# SCFG.net
KiCad netlist of a schematic drawn in EAGLE
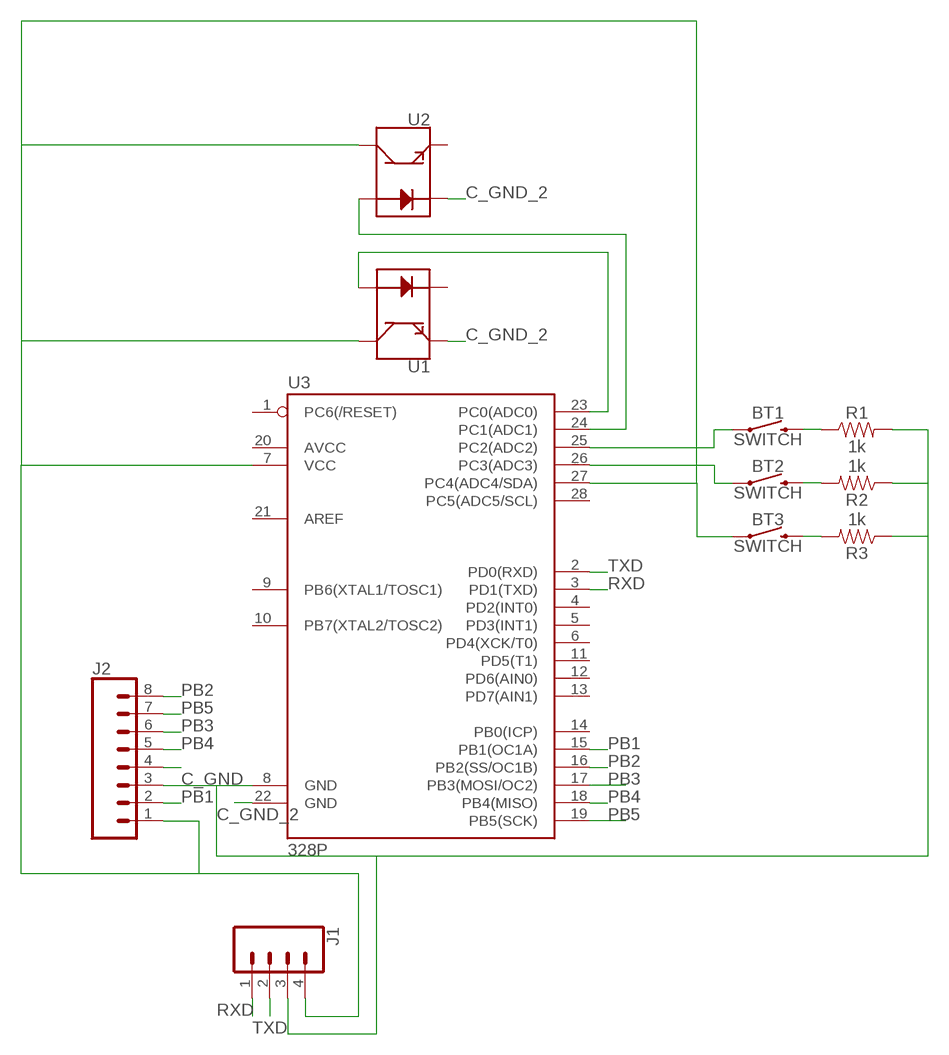
[diagram p0: schematic, sheet 1]

(export (version "E")
  (design (tool "Eeschema 10.0.6"))
  (components
    (comp (ref "BT1")
      (value "SWITCH")
      (footprint "eagle-import:TACTILE_SWITCH_PTH_6.0MM_KIT")
      (libsource (lib "eagle-import") (part "MOMENTARY-SWITCH-SPST-PTH-6.0MM-KIT"))
    )
    (comp (ref "BT2")
      (value "SWITCH")
      (footprint "eagle-import:TACTILE_SWITCH_PTH_6.0MM_KIT")
      (libsource (lib "eagle-import") (part "MOMENTARY-SWITCH-SPST-PTH-6.0MM-KIT"))
    )
    (comp (ref "BT3")
      (value "SWITCH")
      (footprint "eagle-import:TACTILE_SWITCH_PTH_6.0MM_KIT")
      (libsource (lib "eagle-import") (part "MOMENTARY-SWITCH-SPST-PTH-6.0MM-KIT"))
    )
    (comp (ref "J1")
      (value "CONN_04")
      (footprint "eagle-import:1X04")
      (libsource (lib "eagle-import") (part "CONN_04"))
    )
    (comp (ref "J2")
      (value "CONN_08FEMALE_LOCK")
      (footprint "eagle-import:1X08_FEMALE_LOCK")
      (libsource (lib "eagle-import") (part "CONN_08FEMALE_LOCK"))
    )
    (comp (ref "R1")
      (value "1k")
      (footprint "eagle-import:AXIAL-0.3")
      (libsource (lib "eagle-import") (part "1KOHM-HORIZ-1/4W-1%"))
    )
    (comp (ref "R2")
      (value "1k")
      (footprint "eagle-import:AXIAL-0.3")
      (libsource (lib "eagle-import") (part "1KOHM-HORIZ-1/4W-1%"))
    )
    (comp (ref "R3")
      (value "1k")
      (footprint "eagle-import:AXIAL-0.3")
      (libsource (lib "eagle-import") (part "1KOHM-HORIZ-1/4W-1%"))
    )
    (comp (ref "U1")
      (value "QRE1113")
      (footprint "eagle-import:QRE1113")
      (libsource (lib "eagle-import") (part "QRE1113"))
    )
    (comp (ref "U2")
      (value "QRE1113")
      (footprint "eagle-import:QRE1113")
      (libsource (lib "eagle-import") (part "QRE1113"))
    )
    (comp (ref "U3")
      (value "328P")
      (footprint "eagle-import:DIP28")
      (libsource (lib "eagle-import") (part "ATMEGA328P_PDIP"))
    )
  )
  (nets
    (net (code "1") (name "/C_GND") (class "Default")
      (node (ref "J1") (pin "3") (pinfunction "3_3") (pintype "passive"))
      (node (ref "J2") (pin "3") (pinfunction "3_3") (pintype "passive"))
      (node (ref "R1") (pin "P$2") (pinfunction "2_P$2") (pintype "passive"))
      (node (ref "R2") (pin "P$1") (pinfunction "1_P$1") (pintype "passive"))
      (node (ref "R3") (pin "P$1") (pinfunction "1_P$1") (pintype "passive"))
      (node (ref "U3") (pin "8") (pinfunction "GND_8") (pintype "bidirectional"))
    )
    (net (code "2") (name "/C_GND_2") (class "Default")
      (node (ref "U1") (pin "4") (pinfunction "E_4") (pintype "bidirectional"))
      (node (ref "U2") (pin "2") (pinfunction "K_2") (pintype "bidirectional"))
      (node (ref "U3") (pin "22") (pinfunction "GND_22") (pintype "bidirectional"))
    )
    (net (code "3") (name "/PB1") (class "Default")
      (node (ref "J2") (pin "2") (pinfunction "2_2") (pintype "passive"))
      (node (ref "U3") (pin "15") (pinfunction "PB1(OC1A)_15") (pintype "bidirectional"))
    )
    (net (code "4") (name "/PB2") (class "Default")
      (node (ref "J2") (pin "8") (pinfunction "8_8") (pintype "passive"))
      (node (ref "U3") (pin "16") (pinfunction "PB2(SS/OC1B)_16") (pintype "bidirectional"))
    )
    (net (code "5") (name "/PB3") (class "Default")
      (node (ref "J2") (pin "6") (pinfunction "6_6") (pintype "passive"))
      (node (ref "U3") (pin "17") (pinfunction "PB3(MOSI/OC2)_17") (pintype "bidirectional"))
    )
    (net (code "6") (name "/PB4") (class "Default")
      (node (ref "J2") (pin "5") (pinfunction "5_5") (pintype "passive"))
      (node (ref "U3") (pin "18") (pinfunction "PB4(MISO)_18") (pintype "bidirectional"))
    )
    (net (code "7") (name "/PB5") (class "Default")
      (node (ref "J2") (pin "7") (pinfunction "7_7") (pintype "passive"))
      (node (ref "U3") (pin "19") (pinfunction "PB5(SCK)_19") (pintype "bidirectional"))
    )
    (net (code "8") (name "/RXD") (class "Default")
      (node (ref "J1") (pin "1") (pinfunction "1_1") (pintype "passive"))
      (node (ref "U3") (pin "3") (pinfunction "PD1(TXD)_3") (pintype "bidirectional"))
    )
    (net (code "9") (name "/TXD") (class "Default")
      (node (ref "J1") (pin "2") (pinfunction "2_2") (pintype "passive"))
      (node (ref "U3") (pin "2") (pinfunction "PD0(RXD)_2") (pintype "bidirectional"))
    )
    (net (code "10") (name "Net-(BT1-2)") (class "Default")
      (node (ref "BT1") (pin "3") (pinfunction "2_3") (pintype "passive"))
      (node (ref "R1") (pin "P$1") (pinfunction "1_P$1") (pintype "passive"))
    )
    (net (code "11") (name "Net-(BT2-2)") (class "Default")
      (node (ref "BT2") (pin "3") (pinfunction "2_3") (pintype "passive"))
      (node (ref "R2") (pin "P$2") (pinfunction "2_P$2") (pintype "passive"))
    )
    (net (code "12") (name "Net-(BT3-2)") (class "Default")
      (node (ref "BT3") (pin "3") (pinfunction "2_3") (pintype "passive"))
      (node (ref "R3") (pin "P$2") (pinfunction "2_P$2") (pintype "passive"))
    )
    (net (code "13") (name "Net-(U1-A)") (class "Default")
      (node (ref "U1") (pin "1") (pinfunction "A_1") (pintype "bidirectional"))
      (node (ref "U3") (pin "23") (pinfunction "PC0(ADC0)_23") (pintype "bidirectional"))
    )
    (net (code "14") (name "Net-(U1-C)") (class "Default")
      (node (ref "BT1") (pin "1") (pinfunction "1_1") (pintype "passive"))
      (node (ref "BT3") (pin "1") (pinfunction "1_1") (pintype "passive"))
      (node (ref "J1") (pin "4") (pinfunction "4_4") (pintype "passive"))
      (node (ref "J2") (pin "1") (pinfunction "1_1") (pintype "passive"))
      (node (ref "U1") (pin "3") (pinfunction "C_3") (pintype "bidirectional"))
      (node (ref "U2") (pin "3") (pinfunction "C_3") (pintype "bidirectional"))
      (node (ref "U3") (pin "25") (pinfunction "PC2(ADC2)_25") (pintype "bidirectional"))
      (node (ref "U3") (pin "27") (pinfunction "PC4(ADC4/SDA)_27") (pintype "bidirectional"))
      (node (ref "U3") (pin "7") (pinfunction "VCC_7") (pintype "bidirectional"))
    )
    (net (code "15") (name "Net-(U2-A)") (class "Default")
      (node (ref "U2") (pin "1") (pinfunction "A_1") (pintype "bidirectional"))
      (node (ref "U3") (pin "24") (pinfunction "PC1(ADC1)_24") (pintype "bidirectional"))
    )
    (net (code "16") (name "Net-(U3-PC3(ADC3))") (class "Default")
      (node (ref "BT2") (pin "1") (pinfunction "1_1") (pintype "passive"))
      (node (ref "U3") (pin "26") (pinfunction "PC3(ADC3)_26") (pintype "bidirectional"))
    )
    (net (code "17") (name "unconnected-(J2-Pad4)") (class "Default")
      (node (ref "J2") (pin "4") (pinfunction "4_4") (pintype "passive"))
    )
    (net (code "18") (name "unconnected-(U1-K-Pad2)") (class "Default")
      (node (ref "U1") (pin "2") (pinfunction "K_2") (pintype "bidirectional"))
    )
    (net (code "19") (name "unconnected-(U2-E-Pad4)") (class "Default")
      (node (ref "U2") (pin "4") (pinfunction "E_4") (pintype "bidirectional"))
    )
    (net (code "20") (name "unconnected-(U3-AREF-Pad21)") (class "Default")
      (node (ref "U3") (pin "21") (pinfunction "AREF_21") (pintype "bidirectional"))
    )
    (net (code "21") (name "unconnected-(U3-AVCC-Pad20)") (class "Default")
      (node (ref "U3") (pin "20") (pinfunction "AVCC_20") (pintype "bidirectional"))
    )
    (net (code "22") (name "unconnected-(U3-PB0(ICP)-Pad14)") (class "Default")
      (node (ref "U3") (pin "14") (pinfunction "PB0(ICP)_14") (pintype "bidirectional"))
    )
    (net (code "23") (name "unconnected-(U3-PB6(XTAL1{slash}TOSC1)-Pad9)") (class "Default")
      (node (ref "U3") (pin "9") (pinfunction "PB6(XTAL1/TOSC1)_9") (pintype "bidirectional"))
    )
    (net (code "24") (name "unconnected-(U3-PB7(XTAL2{slash}TOSC2)-Pad10)") (class "Default")
      (node (ref "U3") (pin "10") (pinfunction "PB7(XTAL2/TOSC2)_10") (pintype "bidirectional"))
    )
    (net (code "25") (name "unconnected-(U3-PC5(ADC5{slash}SCL)-Pad28)") (class "Default")
      (node (ref "U3") (pin "28") (pinfunction "PC5(ADC5/SCL)_28") (pintype "bidirectional"))
    )
    (net (code "26") (name "unconnected-(U3-PC6({slash}RESET)-Pad1)") (class "Default")
      (node (ref "U3") (pin "1") (pinfunction "PC6(/RESET)_1") (pintype "bidirectional"))
    )
    (net (code "27") (name "unconnected-(U3-PD2(INT0)-Pad4)") (class "Default")
      (node (ref "U3") (pin "4") (pinfunction "PD2(INT0)_4") (pintype "bidirectional"))
    )
    (net (code "28") (name "unconnected-(U3-PD3(INT1)-Pad5)") (class "Default")
      (node (ref "U3") (pin "5") (pinfunction "PD3(INT1)_5") (pintype "bidirectional"))
    )
    (net (code "29") (name "unconnected-(U3-PD4(XCK{slash}T0)-Pad6)") (class "Default")
      (node (ref "U3") (pin "6") (pinfunction "PD4(XCK/T0)_6") (pintype "bidirectional"))
    )
    (net (code "30") (name "unconnected-(U3-PD5(T1)-Pad11)") (class "Default")
      (node (ref "U3") (pin "11") (pinfunction "PD5(T1)_11") (pintype "bidirectional"))
    )
    (net (code "31") (name "unconnected-(U3-PD6(AIN0)-Pad12)") (class "Default")
      (node (ref "U3") (pin "12") (pinfunction "PD6(AIN0)_12") (pintype "bidirectional"))
    )
    (net (code "32") (name "unconnected-(U3-PD7(AIN1)-Pad13)") (class "Default")
      (node (ref "U3") (pin "13") (pinfunction "PD7(AIN1)_13") (pintype "bidirectional"))
    )
  )
)
